# CPU.net
KiCad netlist of a schematic drawn in Altium Designer
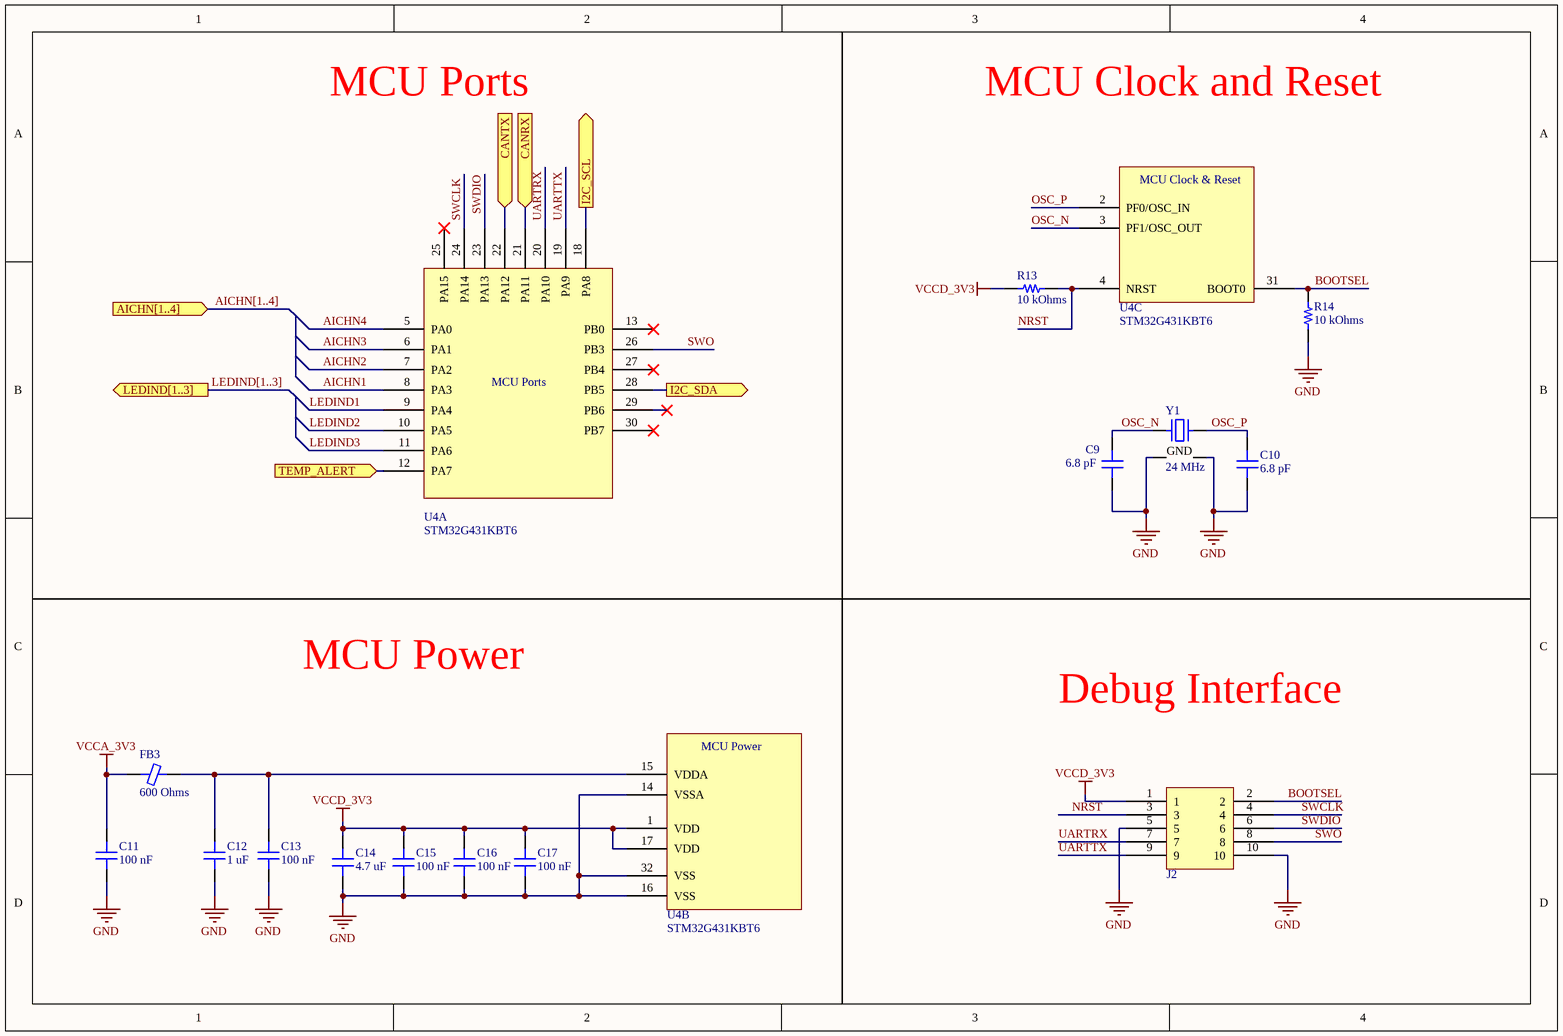
[diagram p0: CPU.SchDoc]

(export (version "E")
  (design (tool "Eeschema 10.0.6"))
  (components
    (comp (ref "C9")
      (value "6.8 pF")
      (footprint "CAP 0603_1608")
      (description "MLCC Ceramic 6.8 pF 50 V 0.25 pF Capacitor")
      (fields (field (name "PART NUMBER") "06035A6R8C4T4A") (field (name "MANUFACTURER") "AVX"))
      (libsource (lib "Database_Libs") (part "Capacitor"))
    )
    (comp (ref "C10")
      (value "6.8 pF")
      (footprint "CAP 0603_1608")
      (description "MLCC Ceramic 6.8 pF 50 V 0.25 pF Capacitor")
      (fields (field (name "PART NUMBER") "06035A6R8C4T4A") (field (name "MANUFACTURER") "AVX"))
      (libsource (lib "Database_Libs") (part "Capacitor"))
    )
    (comp (ref "C11")
      (value "100 nF")
      (footprint "CAP 0603_1608")
      (description "MLCC Ceramic 100 nF 16 V 10% Capacitor")
      (fields (field (name "PART NUMBER") "0603YC104KAT2A") (field (name "MANUFACTURER") "AVX"))
      (libsource (lib "Database_Libs") (part "Capacitor"))
    )
    (comp (ref "C12")
      (value "1 uF")
      (footprint "CAP 0603_1608")
      (description "MLCC Ceramic 1 uF 16 V 10% Capacitor")
      (fields (field (name "PART NUMBER") "0603YC105KAT2A") (field (name "MANUFACTURER") "AVX"))
      (libsource (lib "Database_Libs") (part "Capacitor"))
    )
    (comp (ref "C13")
      (value "100 nF")
      (footprint "CAP 0603_1608")
      (description "MLCC Ceramic 100 nF 16 V 10% Capacitor")
      (fields (field (name "PART NUMBER") "0603YC104KAT2A") (field (name "MANUFACTURER") "AVX"))
      (libsource (lib "Database_Libs") (part "Capacitor"))
    )
    (comp (ref "C14")
      (value "4.7 uF")
      (footprint "CAP 0603_1608")
      (description "MLCC Ceramic 4.7 uF 10 V 20% Capacitor")
      (fields (field (name "PART NUMBER") "GRM188Z71A475ME15D") (field (name "MANUFACTURER") "Murata"))
      (libsource (lib "Database_Libs") (part "Capacitor"))
    )
    (comp (ref "C15")
      (value "100 nF")
      (footprint "CAP 0603_1608")
      (description "MLCC Ceramic 100 nF 16 V 10% Capacitor")
      (fields (field (name "PART NUMBER") "0603YC104KAT2A") (field (name "MANUFACTURER") "AVX"))
      (libsource (lib "Database_Libs") (part "Capacitor"))
    )
    (comp (ref "C16")
      (value "100 nF")
      (footprint "CAP 0603_1608")
      (description "MLCC Ceramic 100 nF 16 V 10% Capacitor")
      (fields (field (name "PART NUMBER") "0603YC104KAT2A") (field (name "MANUFACTURER") "AVX"))
      (libsource (lib "Database_Libs") (part "Capacitor"))
    )
    (comp (ref "C17")
      (value "100 nF")
      (footprint "CAP 0603_1608")
      (description "MLCC Ceramic 100 nF 16 V 10% Capacitor")
      (fields (field (name "PART NUMBER") "0603YC104KAT2A") (field (name "MANUFACTURER") "AVX"))
      (libsource (lib "Database_Libs") (part "Capacitor"))
    )
    (comp (ref "FB3")
      (value "600 Ohms")
      (footprint "FER 0805_2012")
      (description "Ferrite bead")
      (fields
        (field (name "PART NUMBER") "BLM21SP601SH1D")
        (field (name "MANUFACTURER") "Murata Electronics")
      )
      (libsource (lib "Database_Libs") (part "Ferrite Chip"))
    )
    (comp (ref "J2")
      (value "SHF-105-01-L-D-TH")
      (footprint "SHF-105-01-X-D-TH")
      (description "Shrouded Terminal Strip, 0.050 pitch")
      (fields (field (name "MANUFACTURER") "Samtec"))
      (libsource (lib "Database_Libs") (part "CONNECTOR"))
    )
    (comp (ref "R13")
      (value "10 kOhms")
      (footprint "RES 0603_1608")
      (description "Thin Film Resistor 10 kOhms 1%")
      (fields (field (name "PART NUMBER") "CRCW060310K0FKEAC") (field (name "MANUFACTURER") "Vishay / Dale"))
      (libsource (lib "Database_Libs") (part "Resistor"))
    )
    (comp (ref "R14")
      (value "10 kOhms")
      (footprint "RES 0603_1608")
      (description "Thin Film Resistor 10 kOhms 1%")
      (fields (field (name "PART NUMBER") "CRCW060310K0FKEAC") (field (name "MANUFACTURER") "Vishay / Dale"))
      (libsource (lib "Database_Libs") (part "Resistor"))
    )
    (comp (ref "U4")
      (value "STM32G431KBT6")
      (footprint "LQFP32ST")
      (description "STM32G431 ARM Cortex-M4  170MHz MCU")
      (fields (field (name "MANUFACTURER") "STMicroelectronics"))
      (libsource (lib "") (part "STM32G431X_1"))
    )
    (comp (ref "Y1")
      (value "24 MHz")
      (footprint "ABM8G")
      (description "24MHz 8pF -20C +70C 20ppm Crystal Oscillator")
      (fields
        (field (name "PART NUMBER") "ABM8W-24.0000MHZ-8-B1U-T3")
        (field (name "MANUFACTURER") "ABRACON")
      )
      (libsource (lib "Database_Libs") (part "CRYSTAL"))
    )
  )
  (nets
    (net (code "2") (name "/AICHN1") (class "Default")
      (node (ref "U4") (pin "8") (pinfunction "PA3_8") (pintype "passive"))
    )
    (net (code "3") (name "/AICHN2") (class "Default")
      (node (ref "U4") (pin "7") (pinfunction "PA2_7") (pintype "passive"))
    )
    (net (code "4") (name "/AICHN3") (class "Default")
      (node (ref "U4") (pin "6") (pinfunction "PA1_6") (pintype "passive"))
    )
    (net (code "5") (name "/AICHN4") (class "Default")
      (node (ref "U4") (pin "5") (pinfunction "PA0_5") (pintype "passive"))
    )
    (net (code "7") (name "/BOOTSEL") (class "Default")
      (node (ref "J2") (pin "2") (pinfunction "2_2") (pintype "passive"))
      (node (ref "R14") (pin "1") (pinfunction "1_1") (pintype "passive"))
      (node (ref "U4") (pin "31") (pinfunction "BOOT0_31") (pintype "passive"))
    )
    (net (code "8") (name "/CANRX") (class "Default")
      (node (ref "U4") (pin "21") (pinfunction "PA11_21") (pintype "passive"))
    )
    (net (code "9") (name "/CANTX") (class "Default")
      (node (ref "U4") (pin "22") (pinfunction "PA12_22") (pintype "passive"))
    )
    (net (code "10") (name "/I2C_SCL") (class "Default")
      (node (ref "U4") (pin "18") (pinfunction "PA8_18") (pintype "passive"))
    )
    (net (code "11") (name "/I2C_SDA") (class "Default")
      (node (ref "U4") (pin "28") (pinfunction "PB5_28") (pintype "passive"))
    )
    (net (code "12") (name "/LEDIND1") (class "Default")
      (node (ref "U4") (pin "9") (pinfunction "PA4_9") (pintype "passive"))
    )
    (net (code "13") (name "/LEDIND2") (class "Default")
      (node (ref "U4") (pin "10") (pinfunction "PA5_10") (pintype "passive"))
    )
    (net (code "14") (name "/LEDIND3") (class "Default")
      (node (ref "U4") (pin "11") (pinfunction "PA6_11") (pintype "passive"))
    )
    (net (code "16") (name "/NRST") (class "Default")
      (node (ref "J2") (pin "3") (pinfunction "3_3") (pintype "passive"))
      (node (ref "R13") (pin "2") (pinfunction "2_2") (pintype "passive"))
      (node (ref "U4") (pin "4") (pinfunction "NRST_4") (pintype "passive"))
    )
    (net (code "17") (name "/OSC_N") (class "Default")
      (node (ref "C9") (pin "1") (pinfunction "1_1") (pintype "passive"))
      (node (ref "U4") (pin "3") (pinfunction "PF1/OSC_OUT_3") (pintype "passive"))
      (node (ref "Y1") (pin "1") (pinfunction "1_1") (pintype "passive"))
    )
    (net (code "18") (name "/OSC_P") (class "Default")
      (node (ref "C10") (pin "1") (pinfunction "1_1") (pintype "passive"))
      (node (ref "U4") (pin "2") (pinfunction "PF0/OSC_IN_2") (pintype "passive"))
      (node (ref "Y1") (pin "3") (pinfunction "3_3") (pintype "passive"))
    )
    (net (code "19") (name "/SWCLK") (class "Default")
      (node (ref "J2") (pin "4") (pinfunction "4_4") (pintype "passive"))
      (node (ref "U4") (pin "24") (pinfunction "PA14_24") (pintype "passive"))
    )
    (net (code "20") (name "/SWDIO") (class "Default")
      (node (ref "J2") (pin "6") (pinfunction "6_6") (pintype "passive"))
      (node (ref "U4") (pin "23") (pinfunction "PA13_23") (pintype "passive"))
    )
    (net (code "21") (name "/SWO") (class "Default")
      (node (ref "J2") (pin "8") (pinfunction "8_8") (pintype "passive"))
      (node (ref "U4") (pin "26") (pinfunction "PB3_26") (pintype "passive"))
    )
    (net (code "22") (name "/TEMP_ALERT") (class "Default")
      (node (ref "U4") (pin "12") (pinfunction "PA7_12") (pintype "passive"))
    )
    (net (code "23") (name "/UARTRX") (class "Default")
      (node (ref "J2") (pin "7") (pinfunction "7_7") (pintype "passive"))
      (node (ref "U4") (pin "20") (pinfunction "PA10_20") (pintype "passive"))
    )
    (net (code "24") (name "/UARTTX") (class "Default")
      (node (ref "J2") (pin "9") (pinfunction "9_9") (pintype "passive"))
      (node (ref "U4") (pin "19") (pinfunction "PA9_19") (pintype "passive"))
    )
    (net (code "25") (name "GND") (class "Default")
      (node (ref "C10") (pin "2") (pinfunction "2_2") (pintype "passive"))
      (node (ref "C11") (pin "2") (pinfunction "2_2") (pintype "passive"))
      (node (ref "C12") (pin "1") (pinfunction "1_1") (pintype "passive"))
      (node (ref "C13") (pin "2") (pinfunction "2_2") (pintype "passive"))
      (node (ref "C14") (pin "1") (pinfunction "1_1") (pintype "passive"))
      (node (ref "C15") (pin "2") (pinfunction "2_2") (pintype "passive"))
      (node (ref "C16") (pin "2") (pinfunction "2_2") (pintype "passive"))
      (node (ref "C17") (pin "2") (pinfunction "2_2") (pintype "passive"))
      (node (ref "C9") (pin "2") (pinfunction "2_2") (pintype "passive"))
      (node (ref "J2") (pin "10") (pinfunction "10_10") (pintype "passive"))
      (node (ref "J2") (pin "5") (pinfunction "5_5") (pintype "passive"))
      (node (ref "R14") (pin "2") (pinfunction "2_2") (pintype "passive"))
      (node (ref "U4") (pin "14") (pinfunction "VSSA_14") (pintype "passive"))
      (node (ref "U4") (pin "16") (pinfunction "VSS_16") (pintype "passive"))
      (node (ref "U4") (pin "32") (pinfunction "VSS_32") (pintype "passive"))
      (node (ref "Y1") (pin "2") (pinfunction "GND_2") (pintype "passive"))
      (node (ref "Y1") (pin "4") (pinfunction "GND_4") (pintype "passive"))
    )
    (net (code "26") (name "Net-(U4B-VDDA)") (class "Default")
      (node (ref "C12") (pin "2") (pinfunction "2_2") (pintype "passive"))
      (node (ref "C13") (pin "1") (pinfunction "1_1") (pintype "passive"))
      (node (ref "FB3") (pin "1") (pinfunction "1_1") (pintype "passive"))
      (node (ref "U4") (pin "15") (pinfunction "VDDA_15") (pintype "passive"))
    )
    (net (code "27") (name "VCCA_3V3") (class "Default")
      (node (ref "C11") (pin "1") (pinfunction "1_1") (pintype "passive"))
      (node (ref "FB3") (pin "2") (pinfunction "2_2") (pintype "passive"))
    )
    (net (code "28") (name "VCCD_3V3") (class "Default")
      (node (ref "C14") (pin "2") (pinfunction "2_2") (pintype "passive"))
      (node (ref "C15") (pin "1") (pinfunction "1_1") (pintype "passive"))
      (node (ref "C16") (pin "1") (pinfunction "1_1") (pintype "passive"))
      (node (ref "C17") (pin "1") (pinfunction "1_1") (pintype "passive"))
      (node (ref "J2") (pin "1") (pinfunction "1_1") (pintype "passive"))
      (node (ref "R13") (pin "1") (pinfunction "1_1") (pintype "passive"))
      (node (ref "U4") (pin "1") (pinfunction "VDD_1") (pintype "passive"))
      (node (ref "U4") (pin "17") (pinfunction "VDD_17") (pintype "passive"))
    )
    (net (code "29") (name "unconnected-(U4A-PA15-Pad25)") (class "Default")
      (node (ref "U4") (pin "25") (pinfunction "PA15_25") (pintype "passive+no_connect"))
    )
    (net (code "30") (name "unconnected-(U4A-PB0-Pad13)") (class "Default")
      (node (ref "U4") (pin "13") (pinfunction "PB0_13") (pintype "passive+no_connect"))
    )
    (net (code "31") (name "unconnected-(U4A-PB4-Pad27)") (class "Default")
      (node (ref "U4") (pin "27") (pinfunction "PB4_27") (pintype "passive+no_connect"))
    )
    (net (code "32") (name "unconnected-(U4A-PB6-Pad29)") (class "Default")
      (node (ref "U4") (pin "29") (pinfunction "PB6_29") (pintype "passive+no_connect"))
    )
    (net (code "33") (name "unconnected-(U4A-PB7-Pad30)") (class "Default")
      (node (ref "U4") (pin "30") (pinfunction "PB7_30") (pintype "passive+no_connect"))
    )
  )
)
